# NSE2020_1.net
KiCad netlist of a schematic drawn in EAGLE
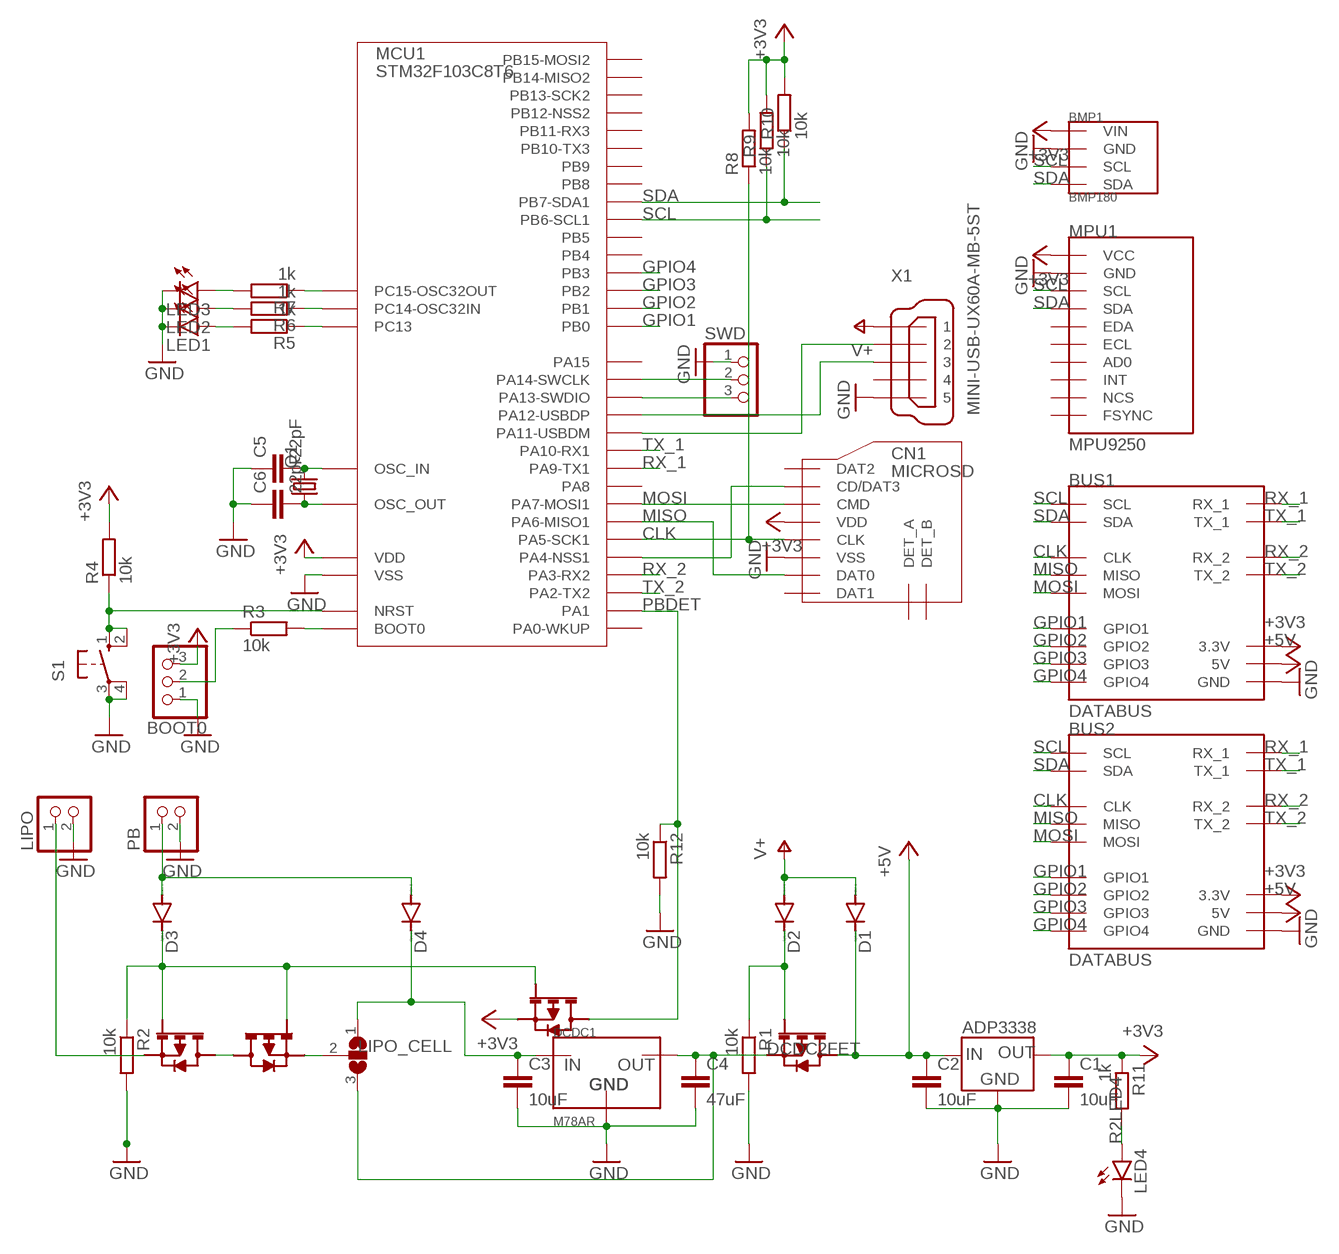
[diagram p0: schematic, sheet 1]

(export (version "E")
  (design (tool "Eeschema 10.0.6"))
  (components
    (comp (ref "BMP1")
      (value "BMP180")
      (footprint "eagle-import:GY-68")
      (libsource (lib "eagle-import") (part "BMP180"))
    )
    (comp (ref "BOOT0")
      (value "PINHD-1X3")
      (footprint "eagle-import:1X03")
      (libsource (lib "eagle-import") (part "PINHD-1X3"))
    )
    (comp (ref "BUS1")
      (value "DATABUS")
      (footprint "eagle-import:8X2")
      (libsource (lib "eagle-import") (part "DATABUS"))
    )
    (comp (ref "BUS2")
      (value "DATABUS")
      (footprint "eagle-import:8X2")
      (libsource (lib "eagle-import") (part "DATABUS"))
    )
    (comp (ref "C1")
      (value "10uF")
      (footprint "eagle-import:C2012")
      (libsource (lib "eagle-import") (part "C-EUC2012"))
    )
    (comp (ref "C2")
      (value "10uF")
      (footprint "eagle-import:C2012")
      (libsource (lib "eagle-import") (part "C-EUC2012"))
    )
    (comp (ref "C3")
      (value "10uF")
      (footprint "eagle-import:C2012")
      (libsource (lib "eagle-import") (part "C-EUC2012"))
    )
    (comp (ref "C4")
      (value "47uF")
      (footprint "eagle-import:C2012")
      (libsource (lib "eagle-import") (part "C-EUC2012"))
    )
    (comp (ref "C5")
      (value "22pF")
      (footprint "eagle-import:C2012")
      (libsource (lib "eagle-import") (part "C-EUC2012"))
    )
    (comp (ref "C6")
      (value "22pF")
      (footprint "eagle-import:C2012")
      (libsource (lib "eagle-import") (part "C-EUC2012"))
    )
    (comp (ref "CN1")
      (value "MICROSD")
      (footprint "eagle-import:DM3AT")
      (libsource (lib "eagle-import") (part "MICROSD"))
    )
    (comp (ref "D1")
      (value "DIODE-SOD123")
      (footprint "eagle-import:SOD123")
      (libsource (lib "eagle-import") (part "DIODE-SOD123"))
    )
    (comp (ref "D2")
      (value "DIODE-SOD123")
      (footprint "eagle-import:SOD123")
      (libsource (lib "eagle-import") (part "DIODE-SOD123"))
    )
    (comp (ref "D3")
      (value "DIODE-SOD123")
      (footprint "eagle-import:SOD123")
      (libsource (lib "eagle-import") (part "DIODE-SOD123"))
    )
    (comp (ref "D4")
      (value "DIODE-SOD123")
      (footprint "eagle-import:SOD123")
      (libsource (lib "eagle-import") (part "DIODE-SOD123"))
    )
    (comp (ref "DCDC1")
      (value "M78AR")
      (footprint "eagle-import:M78AR")
      (libsource (lib "eagle-import") (part "M78AR"))
    )
    (comp (ref "IC1")
      (value "ADP3338-3.3")
      (footprint "eagle-import:SOT-223")
      (libsource (lib "eagle-import") (part "ADP3338-3.3"))
    )
    (comp (ref "LED1")
      (value "LEDSMT1206")
      (footprint "eagle-import:1206")
      (libsource (lib "eagle-import") (part "LEDSMT1206"))
    )
    (comp (ref "LED2")
      (value "LEDSMT1206")
      (footprint "eagle-import:1206")
      (libsource (lib "eagle-import") (part "LEDSMT1206"))
    )
    (comp (ref "LED3")
      (value "LEDSMT1206")
      (footprint "eagle-import:1206")
      (libsource (lib "eagle-import") (part "LEDSMT1206"))
    )
    (comp (ref "LED4")
      (value "LEDSMT1206")
      (footprint "eagle-import:1206")
      (libsource (lib "eagle-import") (part "LEDSMT1206"))
    )
    (comp (ref "LIPO")
      (value "PINHD-1X2")
      (footprint "eagle-import:1X02")
      (libsource (lib "eagle-import") (part "PINHD-1X2"))
    )
    (comp (ref "LIPO_CELL")
      (value "SJ2W")
      (footprint "eagle-import:SJ_2")
      (libsource (lib "eagle-import") (part "SJ2W"))
    )
    (comp (ref "MCU1")
      (value "STM32F103C8T6")
      (footprint "eagle-import:LQFP48")
      (libsource (lib "eagle-import") (part "STM32F103C8T6"))
    )
    (comp (ref "MPU1")
      (value "MPU9250")
      (footprint "eagle-import:GY-9250")
      (libsource (lib "eagle-import") (part "MPU9250"))
    )
    (comp (ref "PB")
      (value "PINHD-1X2")
      (footprint "eagle-import:1X02")
      (libsource (lib "eagle-import") (part "PINHD-1X2"))
    )
    (comp (ref "Q1")
      (value "CRYSTALHC49S")
      (footprint "eagle-import:HC49_S")
      (libsource (lib "eagle-import") (part "CRYSTALHC49S"))
    )
    (comp (ref "R1")
      (value "10k")
      (footprint "eagle-import:M2012")
      (libsource (lib "eagle-import") (part "R-EU_M2012"))
    )
    (comp (ref "R2")
      (value "10k")
      (footprint "eagle-import:M2012")
      (libsource (lib "eagle-import") (part "R-EU_M2012"))
    )
    (comp (ref "R3")
      (value "10k")
      (footprint "eagle-import:M2012")
      (libsource (lib "eagle-import") (part "R-EU_M2012"))
    )
    (comp (ref "R4")
      (value "10k")
      (footprint "eagle-import:M2012")
      (libsource (lib "eagle-import") (part "R-EU_M2012"))
    )
    (comp (ref "R5")
      (value "1k")
      (footprint "eagle-import:M2012")
      (libsource (lib "eagle-import") (part "R-EU_M2012"))
    )
    (comp (ref "R6")
      (value "1k")
      (footprint "eagle-import:M2012")
      (libsource (lib "eagle-import") (part "R-EU_M2012"))
    )
    (comp (ref "R7")
      (value "1k")
      (footprint "eagle-import:M2012")
      (libsource (lib "eagle-import") (part "R-EU_M2012"))
    )
    (comp (ref "R8")
      (value "10k")
      (footprint "eagle-import:M2012")
      (libsource (lib "eagle-import") (part "R-EU_M2012"))
    )
    (comp (ref "R9")
      (value "10k")
      (footprint "eagle-import:M2012")
      (libsource (lib "eagle-import") (part "R-EU_M2012"))
    )
    (comp (ref "R10")
      (value "10k")
      (footprint "eagle-import:M2012")
      (libsource (lib "eagle-import") (part "R-EU_M2012"))
    )
    (comp (ref "R11")
      (value "1k")
      (footprint "eagle-import:M2012")
      (libsource (lib "eagle-import") (part "R-EU_M2012"))
    )
    (comp (ref "R12")
      (value "10k")
      (footprint "eagle-import:M2012")
      (libsource (lib "eagle-import") (part "R-EU_M2012"))
    )
    (comp (ref "S1")
      (value "10-XX")
      (footprint "eagle-import:B3F-10XX")
      (fields (field (name "MPN") "B3F-1000"))
      (libsource (lib "eagle-import") (part "10-XX"))
    )
    (comp (ref "SWD")
      (value "PINHD-1X3")
      (footprint "eagle-import:1X03")
      (libsource (lib "eagle-import") (part "PINHD-1X3"))
    )
    (comp (ref "U$1")
      (value "2SJ681")
      (footprint "eagle-import:2SJ681")
      (libsource (lib "eagle-import") (part "2SJ681"))
    )
    (comp (ref "U$2")
      (value "2SJ681")
      (footprint "eagle-import:2SJ681")
      (libsource (lib "eagle-import") (part "2SJ681"))
    )
    (comp (ref "U$3")
      (value "2SJ681")
      (footprint "eagle-import:2SJ681")
      (libsource (lib "eagle-import") (part "2SJ681"))
    )
    (comp (ref "U$4")
      (value "2SJ681")
      (footprint "eagle-import:2SJ681")
      (libsource (lib "eagle-import") (part "2SJ681"))
    )
    (comp (ref "X1")
      (value "MINI-USB-UX60A-MB-5ST")
      (footprint "eagle-import:UX60A-MB-5ST")
      (libsource (lib "eagle-import") (part "MINI-USB-UX60A-MB-5ST"))
    )
  )
  (nets
    (net (code "1") (name "+3V3") (class "Default")
      (node (ref "BMP1") (pin "P1") (pinfunction "VIN_P1") (pintype "bidirectional"))
      (node (ref "BOOT0") (pin "3") (pinfunction "3_3") (pintype "passive"))
      (node (ref "BUS1") (pin "P6") (pinfunction "3.3V_P6") (pintype "bidirectional"))
      (node (ref "BUS2") (pin "P6") (pinfunction "3.3V_P6") (pintype "bidirectional"))
      (node (ref "C1") (pin "1") (pinfunction "1_1") (pintype "passive"))
      (node (ref "CN1") (pin "VDD") (pinfunction "VDD_VDD") (pintype "bidirectional"))
      (node (ref "IC1") (pin "1") (pinfunction "OUT_1") (pintype "output"))
      (node (ref "IC1") (pin "2") (pinfunction "OUT_2") (pintype "output"))
      (node (ref "MCU1") (pin "1") (pinfunction "VDD_1") (pintype "bidirectional"))
      (node (ref "MCU1") (pin "24") (pinfunction "VDD_24") (pintype "bidirectional"))
      (node (ref "MCU1") (pin "36") (pinfunction "VDD_36") (pintype "bidirectional"))
      (node (ref "MCU1") (pin "48") (pinfunction "VDD_48") (pintype "bidirectional"))
      (node (ref "MCU1") (pin "9") (pinfunction "VDD_9") (pintype "bidirectional"))
      (node (ref "MPU1") (pin "P1") (pinfunction "VCC_P1") (pintype "bidirectional"))
      (node (ref "R10") (pin "2") (pinfunction "2_2") (pintype "passive"))
      (node (ref "R11") (pin "1") (pinfunction "1_1") (pintype "passive"))
      (node (ref "R4") (pin "2") (pinfunction "2_2") (pintype "passive"))
      (node (ref "R8") (pin "2") (pinfunction "2_2") (pintype "passive"))
      (node (ref "R9") (pin "2") (pinfunction "2_2") (pintype "passive"))
      (node (ref "U$4") (pin "P$3") (pinfunction "P$3_P$3") (pintype "bidirectional"))
    )
    (net (code "2") (name "+5V") (class "Default")
      (node (ref "BUS1") (pin "P7") (pinfunction "5V_P7") (pintype "bidirectional"))
      (node (ref "BUS2") (pin "P7") (pinfunction "5V_P7") (pintype "bidirectional"))
      (node (ref "C2") (pin "1") (pinfunction "1_1") (pintype "passive"))
      (node (ref "D1") (pin "C") (pinfunction "C_C") (pintype "passive"))
      (node (ref "IC1") (pin "3") (pinfunction "IN_3") (pintype "input"))
      (node (ref "U$1") (pin "P$2") (pinfunction "P$1_P$2") (pintype "bidirectional"))
      (node (ref "U$1") (pin "P$4") (pinfunction "P$1_P$4") (pintype "bidirectional"))
    )
    (net (code "3") (name "/CLK") (class "Default")
      (node (ref "BUS1") (pin "P1") (pinfunction "CLK_P1") (pintype "bidirectional"))
      (node (ref "BUS2") (pin "P1") (pinfunction "CLK_P1") (pintype "bidirectional"))
      (node (ref "CN1") (pin "CLK") (pinfunction "CLK_CLK") (pintype "bidirectional"))
      (node (ref "MCU1") (pin "15") (pinfunction "PA5-SCK1_15") (pintype "bidirectional"))
      (node (ref "R8") (pin "1") (pinfunction "1_1") (pintype "passive"))
    )
    (net (code "4") (name "/DCDC2FET") (class "Default")
      (node (ref "C4") (pin "1") (pinfunction "1_1") (pintype "passive"))
      (node (ref "DCDC1") (pin "P3") (pinfunction "OUT_P3") (pintype "bidirectional"))
      (node (ref "LIPO_CELL") (pin "3") (pinfunction "3_3") (pintype "passive"))
      (node (ref "U$1") (pin "P$3") (pinfunction "P$3_P$3") (pintype "bidirectional"))
    )
    (net (code "5") (name "/GPIO1") (class "Default")
      (node (ref "BUS1") (pin "P3") (pinfunction "GPIO1_P3") (pintype "bidirectional"))
      (node (ref "BUS2") (pin "P3") (pinfunction "GPIO1_P3") (pintype "bidirectional"))
      (node (ref "MCU1") (pin "18") (pinfunction "PB0_18") (pintype "bidirectional"))
    )
    (net (code "6") (name "/GPIO2") (class "Default")
      (node (ref "BUS1") (pin "P10") (pinfunction "GPIO2_P10") (pintype "bidirectional"))
      (node (ref "BUS2") (pin "P10") (pinfunction "GPIO2_P10") (pintype "bidirectional"))
      (node (ref "MCU1") (pin "19") (pinfunction "PB1_19") (pintype "bidirectional"))
    )
    (net (code "7") (name "/GPIO3") (class "Default")
      (node (ref "BUS1") (pin "P14") (pinfunction "GPIO3_P14") (pintype "bidirectional"))
      (node (ref "BUS2") (pin "P14") (pinfunction "GPIO3_P14") (pintype "bidirectional"))
      (node (ref "MCU1") (pin "20") (pinfunction "PB2_20") (pintype "bidirectional"))
    )
    (net (code "8") (name "/GPIO4") (class "Default")
      (node (ref "BUS1") (pin "P15") (pinfunction "GPIO4_P15") (pintype "bidirectional"))
      (node (ref "BUS2") (pin "P15") (pinfunction "GPIO4_P15") (pintype "bidirectional"))
      (node (ref "MCU1") (pin "39") (pinfunction "PB3_39") (pintype "bidirectional"))
    )
    (net (code "9") (name "/MISO") (class "Default")
      (node (ref "BUS1") (pin "P12") (pinfunction "MISO_P12") (pintype "bidirectional"))
      (node (ref "BUS2") (pin "P12") (pinfunction "MISO_P12") (pintype "bidirectional"))
      (node (ref "CN1") (pin "DAT0") (pinfunction "DAT0_DAT0") (pintype "bidirectional"))
      (node (ref "MCU1") (pin "16") (pinfunction "PA6-MISO1_16") (pintype "bidirectional"))
    )
    (net (code "10") (name "/MOSI") (class "Default")
      (node (ref "BUS1") (pin "P2") (pinfunction "MOSI_P2") (pintype "bidirectional"))
      (node (ref "BUS2") (pin "P2") (pinfunction "MOSI_P2") (pintype "bidirectional"))
      (node (ref "CN1") (pin "CMD") (pinfunction "CMD_CMD") (pintype "bidirectional"))
      (node (ref "MCU1") (pin "17") (pinfunction "PA7-MOSI1_17") (pintype "bidirectional"))
    )
    (net (code "11") (name "/PBDET") (class "Default")
      (node (ref "MCU1") (pin "11") (pinfunction "PA1_11") (pintype "bidirectional"))
      (node (ref "R12") (pin "1") (pinfunction "1_1") (pintype "passive"))
      (node (ref "U$4") (pin "P$2") (pinfunction "P$1_P$2") (pintype "bidirectional"))
      (node (ref "U$4") (pin "P$4") (pinfunction "P$1_P$4") (pintype "bidirectional"))
    )
    (net (code "12") (name "/R2LED4") (class "Default")
      (node (ref "LED4") (pin "A") (pinfunction "A_A") (pintype "passive"))
      (node (ref "R11") (pin "2") (pinfunction "2_2") (pintype "passive"))
    )
    (net (code "13") (name "/RX_1") (class "Default")
      (node (ref "BUS1") (pin "P4") (pinfunction "RX_1_P4") (pintype "bidirectional"))
      (node (ref "BUS2") (pin "P4") (pinfunction "RX_1_P4") (pintype "bidirectional"))
      (node (ref "MCU1") (pin "30") (pinfunction "PA9-TX1_30") (pintype "bidirectional"))
    )
    (net (code "14") (name "/RX_2") (class "Default")
      (node (ref "BUS1") (pin "P9") (pinfunction "RX_2_P9") (pintype "bidirectional"))
      (node (ref "BUS2") (pin "P9") (pinfunction "RX_2_P9") (pintype "bidirectional"))
      (node (ref "MCU1") (pin "13") (pinfunction "PA3-RX2_13") (pintype "bidirectional"))
    )
    (net (code "15") (name "/SCL") (class "Default")
      (node (ref "BMP1") (pin "P3") (pinfunction "SCL_P3") (pintype "bidirectional"))
      (node (ref "BUS1") (pin "P0") (pinfunction "SCL_P0") (pintype "bidirectional"))
      (node (ref "BUS2") (pin "P0") (pinfunction "SCL_P0") (pintype "bidirectional"))
      (node (ref "MCU1") (pin "42") (pinfunction "PB6-SCL1_42") (pintype "bidirectional"))
      (node (ref "MPU1") (pin "P3") (pinfunction "SCL_P3") (pintype "bidirectional"))
      (node (ref "R9") (pin "1") (pinfunction "1_1") (pintype "passive"))
    )
    (net (code "16") (name "/SDA") (class "Default")
      (node (ref "BMP1") (pin "P4") (pinfunction "SDA_P4") (pintype "bidirectional"))
      (node (ref "BUS1") (pin "P13") (pinfunction "SDA_P13") (pintype "bidirectional"))
      (node (ref "BUS2") (pin "P13") (pinfunction "SDA_P13") (pintype "bidirectional"))
      (node (ref "MCU1") (pin "43") (pinfunction "PB7-SDA1_43") (pintype "bidirectional"))
      (node (ref "MPU1") (pin "P4") (pinfunction "SDA_P4") (pintype "bidirectional"))
      (node (ref "R10") (pin "1") (pinfunction "1_1") (pintype "passive"))
    )
    (net (code "17") (name "/TX_1") (class "Default")
      (node (ref "BUS1") (pin "P5") (pinfunction "TX_1_P5") (pintype "bidirectional"))
      (node (ref "BUS2") (pin "P5") (pinfunction "TX_1_P5") (pintype "bidirectional"))
      (node (ref "MCU1") (pin "31") (pinfunction "PA10-RX1_31") (pintype "bidirectional"))
    )
    (net (code "18") (name "/TX_2") (class "Default")
      (node (ref "BUS1") (pin "P8") (pinfunction "TX_2_P8") (pintype "bidirectional"))
      (node (ref "BUS2") (pin "P8") (pinfunction "TX_2_P8") (pintype "bidirectional"))
      (node (ref "MCU1") (pin "12") (pinfunction "PA2-TX2_12") (pintype "bidirectional"))
    )
    (net (code "19") (name "GND") (class "Default")
      (node (ref "BMP1") (pin "P2") (pinfunction "GND_P2") (pintype "bidirectional"))
      (node (ref "BOOT0") (pin "1") (pinfunction "1_1") (pintype "passive"))
      (node (ref "BUS1") (pin "P11") (pinfunction "GND_P11") (pintype "bidirectional"))
      (node (ref "BUS2") (pin "P11") (pinfunction "GND_P11") (pintype "bidirectional"))
      (node (ref "C1") (pin "2") (pinfunction "2_2") (pintype "passive"))
      (node (ref "C2") (pin "2") (pinfunction "2_2") (pintype "passive"))
      (node (ref "C3") (pin "2") (pinfunction "2_2") (pintype "passive"))
      (node (ref "C4") (pin "2") (pinfunction "2_2") (pintype "passive"))
      (node (ref "C5") (pin "1") (pinfunction "1_1") (pintype "passive"))
      (node (ref "C6") (pin "1") (pinfunction "1_1") (pintype "passive"))
      (node (ref "CN1") (pin "VSS") (pinfunction "VSS_VSS") (pintype "bidirectional"))
      (node (ref "DCDC1") (pin "P2") (pinfunction "GND_P2") (pintype "bidirectional"))
      (node (ref "IC1") (pin "4") (pinfunction "GND_4") (pintype "bidirectional"))
      (node (ref "LED1") (pin "C") (pinfunction "C_C") (pintype "passive"))
      (node (ref "LED2") (pin "C") (pinfunction "C_C") (pintype "passive"))
      (node (ref "LED3") (pin "C") (pinfunction "C_C") (pintype "passive"))
      (node (ref "LED4") (pin "C") (pinfunction "C_C") (pintype "passive"))
      (node (ref "LIPO") (pin "2") (pinfunction "2_2") (pintype "passive"))
      (node (ref "MCU1") (pin "23") (pinfunction "VSS_23") (pintype "bidirectional"))
      (node (ref "MCU1") (pin "35") (pinfunction "VSS_35") (pintype "bidirectional"))
      (node (ref "MCU1") (pin "47") (pinfunction "VSS_47") (pintype "bidirectional"))
      (node (ref "MCU1") (pin "8") (pinfunction "VSS_8") (pintype "bidirectional"))
      (node (ref "MPU1") (pin "P10") (pinfunction "GND_P10") (pintype "bidirectional"))
      (node (ref "PB") (pin "2") (pinfunction "2_2") (pintype "passive"))
      (node (ref "R1") (pin "2") (pinfunction "2_2") (pintype "passive"))
      (node (ref "R12") (pin "2") (pinfunction "2_2") (pintype "passive"))
      (node (ref "R2") (pin "2") (pinfunction "2_2") (pintype "passive"))
      (node (ref "S1") (pin "3") (pinfunction "P_3") (pintype "passive"))
      (node (ref "S1") (pin "4") (pinfunction "P1_4") (pintype "passive"))
      (node (ref "SWD") (pin "1") (pinfunction "1_1") (pintype "passive"))
      (node (ref "X1") (pin "5") (pinfunction "5_5") (pintype "input"))
    )
    (net (code "20") (name "Net-(BOOT0-Pad2)") (class "Default")
      (node (ref "BOOT0") (pin "2") (pinfunction "2_2") (pintype "passive"))
      (node (ref "R3") (pin "1") (pinfunction "1_1") (pintype "passive"))
    )
    (net (code "21") (name "Net-(D3-PadA)") (class "Default")
      (node (ref "D3") (pin "A") (pinfunction "A_A") (pintype "passive"))
      (node (ref "D4") (pin "A") (pinfunction "A_A") (pintype "passive"))
      (node (ref "PB") (pin "1") (pinfunction "1_1") (pintype "passive"))
    )
    (net (code "22") (name "Net-(DCDC1-IN)") (class "Default")
      (node (ref "C3") (pin "1") (pinfunction "1_1") (pintype "passive"))
      (node (ref "D4") (pin "C") (pinfunction "C_C") (pintype "passive"))
      (node (ref "DCDC1") (pin "P1") (pinfunction "IN_P1") (pintype "bidirectional"))
      (node (ref "LIPO_CELL") (pin "1") (pinfunction "1_1") (pintype "passive"))
    )
    (net (code "23") (name "Net-(LED1-PadA)") (class "Default")
      (node (ref "LED1") (pin "A") (pinfunction "A_A") (pintype "passive"))
      (node (ref "R5") (pin "2") (pinfunction "2_2") (pintype "passive"))
    )
    (net (code "24") (name "Net-(LED2-PadA)") (class "Default")
      (node (ref "LED2") (pin "A") (pinfunction "A_A") (pintype "passive"))
      (node (ref "R6") (pin "2") (pinfunction "2_2") (pintype "passive"))
    )
    (net (code "25") (name "Net-(LED3-PadA)") (class "Default")
      (node (ref "LED3") (pin "A") (pinfunction "A_A") (pintype "passive"))
      (node (ref "R7") (pin "2") (pinfunction "2_2") (pintype "passive"))
    )
    (net (code "26") (name "Net-(LIPO-Pad1)") (class "Default")
      (node (ref "LIPO") (pin "1") (pinfunction "1_1") (pintype "passive"))
      (node (ref "U$3") (pin "P$3") (pinfunction "P$3_P$3") (pintype "bidirectional"))
    )
    (net (code "27") (name "Net-(LIPO_CELL-Pad2)") (class "Default")
      (node (ref "LIPO_CELL") (pin "2") (pinfunction "2_2") (pintype "passive"))
      (node (ref "U$2") (pin "P$3") (pinfunction "P$3_P$3") (pintype "bidirectional"))
    )
    (net (code "28") (name "Net-(MCU1-BOOT0)") (class "Default")
      (node (ref "MCU1") (pin "44") (pinfunction "BOOT0_44") (pintype "bidirectional"))
      (node (ref "R3") (pin "2") (pinfunction "2_2") (pintype "passive"))
    )
    (net (code "29") (name "Net-(MCU1-NRST)") (class "Default")
      (node (ref "MCU1") (pin "7") (pinfunction "NRST_7") (pintype "bidirectional"))
      (node (ref "R4") (pin "1") (pinfunction "1_1") (pintype "passive"))
      (node (ref "S1") (pin "1") (pinfunction "S_1") (pintype "passive"))
      (node (ref "S1") (pin "2") (pinfunction "S1_2") (pintype "passive"))
    )
    (net (code "30") (name "Net-(MCU1-OSC_IN)") (class "Default")
      (node (ref "C5") (pin "2") (pinfunction "2_2") (pintype "passive"))
      (node (ref "MCU1") (pin "5") (pinfunction "OSC_IN_5") (pintype "bidirectional"))
      (node (ref "Q1") (pin "2") (pinfunction "2_2") (pintype "passive"))
    )
    (net (code "31") (name "Net-(MCU1-OSC_OUT)") (class "Default")
      (node (ref "C6") (pin "2") (pinfunction "2_2") (pintype "passive"))
      (node (ref "MCU1") (pin "6") (pinfunction "OSC_OUT_6") (pintype "bidirectional"))
      (node (ref "Q1") (pin "1") (pinfunction "1_1") (pintype "passive"))
    )
    (net (code "32") (name "Net-(MCU1-PA4-NSS1)") (class "Default")
      (node (ref "CN1") (pin "CD/DAT3") (pinfunction "CD/DAT3_CD/DAT3") (pintype "bidirectional"))
      (node (ref "MCU1") (pin "14") (pinfunction "PA4-NSS1_14") (pintype "bidirectional"))
    )
    (net (code "33") (name "Net-(MCU1-PA11-USBDM)") (class "Default")
      (node (ref "MCU1") (pin "32") (pinfunction "PA11-USBDM_32") (pintype "bidirectional"))
      (node (ref "X1") (pin "2") (pinfunction "2_2") (pintype "input"))
    )
    (net (code "34") (name "Net-(MCU1-PA12-USBDP)") (class "Default")
      (node (ref "MCU1") (pin "33") (pinfunction "PA12-USBDP_33") (pintype "bidirectional"))
      (node (ref "X1") (pin "3") (pinfunction "3_3") (pintype "input"))
    )
    (net (code "35") (name "Net-(MCU1-PA13-SWDIO)") (class "Default")
      (node (ref "MCU1") (pin "34") (pinfunction "PA13-SWDIO_34") (pintype "bidirectional"))
      (node (ref "SWD") (pin "3") (pinfunction "3_3") (pintype "passive"))
    )
    (net (code "36") (name "Net-(MCU1-PA14-SWCLK)") (class "Default")
      (node (ref "MCU1") (pin "37") (pinfunction "PA14-SWCLK_37") (pintype "bidirectional"))
      (node (ref "SWD") (pin "2") (pinfunction "2_2") (pintype "passive"))
    )
    (net (code "37") (name "Net-(MCU1-PC13)") (class "Default")
      (node (ref "MCU1") (pin "2") (pinfunction "PC13_2") (pintype "bidirectional"))
      (node (ref "R5") (pin "1") (pinfunction "1_1") (pintype "passive"))
    )
    (net (code "38") (name "Net-(MCU1-PC14-OSC32IN)") (class "Default")
      (node (ref "MCU1") (pin "3") (pinfunction "PC14-OSC32IN_3") (pintype "bidirectional"))
      (node (ref "R6") (pin "1") (pinfunction "1_1") (pintype "passive"))
    )
    (net (code "39") (name "Net-(MCU1-PC15-OSC32OUT)") (class "Default")
      (node (ref "MCU1") (pin "4") (pinfunction "PC15-OSC32OUT_4") (pintype "bidirectional"))
      (node (ref "R7") (pin "1") (pinfunction "1_1") (pintype "passive"))
    )
    (net (code "40") (name "Net-(U$1-P$2)") (class "Default")
      (node (ref "D2") (pin "C") (pinfunction "C_C") (pintype "passive"))
      (node (ref "R1") (pin "1") (pinfunction "1_1") (pintype "passive"))
      (node (ref "U$1") (pin "P$1") (pinfunction "P$2_P$1") (pintype "bidirectional"))
    )
    (net (code "41") (name "Net-(U$2-P$1-PadP$2)") (class "Default")
      (node (ref "U$2") (pin "P$2") (pinfunction "P$1_P$2") (pintype "bidirectional"))
      (node (ref "U$2") (pin "P$4") (pinfunction "P$1_P$4") (pintype "bidirectional"))
      (node (ref "U$3") (pin "P$2") (pinfunction "P$1_P$2") (pintype "bidirectional"))
      (node (ref "U$3") (pin "P$4") (pinfunction "P$1_P$4") (pintype "bidirectional"))
    )
    (net (code "42") (name "Net-(U$2-P$2)") (class "Default")
      (node (ref "D3") (pin "C") (pinfunction "C_C") (pintype "passive"))
      (node (ref "R2") (pin "1") (pinfunction "1_1") (pintype "passive"))
      (node (ref "U$2") (pin "P$1") (pinfunction "P$2_P$1") (pintype "bidirectional"))
      (node (ref "U$3") (pin "P$1") (pinfunction "P$2_P$1") (pintype "bidirectional"))
      (node (ref "U$4") (pin "P$1") (pinfunction "P$2_P$1") (pintype "bidirectional"))
    )
    (net (code "43") (name "V+") (class "Default")
      (node (ref "D1") (pin "A") (pinfunction "A_A") (pintype "passive"))
      (node (ref "D2") (pin "A") (pinfunction "A_A") (pintype "passive"))
      (node (ref "X1") (pin "1") (pinfunction "1_1") (pintype "input"))
    )
    (net (code "44") (name "unconnected-(CN1-PadDAT1)") (class "Default")
      (node (ref "CN1") (pin "DAT1") (pinfunction "DAT1_DAT1") (pintype "bidirectional"))
    )
    (net (code "45") (name "unconnected-(CN1-PadDAT2)") (class "Default")
      (node (ref "CN1") (pin "DAT2") (pinfunction "DAT2_DAT2") (pintype "bidirectional"))
    )
    (net (code "46") (name "unconnected-(CN1-PadDET_A)") (class "Default")
      (node (ref "CN1") (pin "DET_A") (pinfunction "DET_A_DET_A") (pintype "bidirectional"))
    )
    (net (code "47") (name "unconnected-(CN1-PadDET_B)") (class "Default")
      (node (ref "CN1") (pin "DET_B") (pinfunction "DET_B_DET_B") (pintype "bidirectional"))
    )
    (net (code "48") (name "unconnected-(MCU1-PA0-WKUP-Pad10)") (class "Default")
      (node (ref "MCU1") (pin "10") (pinfunction "PA0-WKUP_10") (pintype "bidirectional"))
    )
    (net (code "49") (name "unconnected-(MCU1-PA8-Pad29)") (class "Default")
      (node (ref "MCU1") (pin "29") (pinfunction "PA8_29") (pintype "bidirectional"))
    )
    (net (code "50") (name "unconnected-(MCU1-PA15-Pad38)") (class "Default")
      (node (ref "MCU1") (pin "38") (pinfunction "PA15_38") (pintype "bidirectional"))
    )
    (net (code "51") (name "unconnected-(MCU1-PB4-Pad40)") (class "Default")
      (node (ref "MCU1") (pin "40") (pinfunction "PB4_40") (pintype "bidirectional"))
    )
    (net (code "52") (name "unconnected-(MCU1-PB5-Pad41)") (class "Default")
      (node (ref "MCU1") (pin "41") (pinfunction "PB5_41") (pintype "bidirectional"))
    )
    (net (code "53") (name "unconnected-(MCU1-PB8-Pad45)") (class "Default")
      (node (ref "MCU1") (pin "45") (pinfunction "PB8_45") (pintype "bidirectional"))
    )
    (net (code "54") (name "unconnected-(MCU1-PB9-Pad46)") (class "Default")
      (node (ref "MCU1") (pin "46") (pinfunction "PB9_46") (pintype "bidirectional"))
    )
    (net (code "55") (name "unconnected-(MCU1-PB10-TX3-Pad21)") (class "Default")
      (node (ref "MCU1") (pin "21") (pinfunction "PB10-TX3_21") (pintype "bidirectional"))
    )
    (net (code "56") (name "unconnected-(MCU1-PB11-RX3-Pad22)") (class "Default")
      (node (ref "MCU1") (pin "22") (pinfunction "PB11-RX3_22") (pintype "bidirectional"))
    )
    (net (code "57") (name "unconnected-(MCU1-PB12-NSS2-Pad25)") (class "Default")
      (node (ref "MCU1") (pin "25") (pinfunction "PB12-NSS2_25") (pintype "bidirectional"))
    )
    (net (code "58") (name "unconnected-(MCU1-PB13-SCK2-Pad26)") (class "Default")
      (node (ref "MCU1") (pin "26") (pinfunction "PB13-SCK2_26") (pintype "bidirectional"))
    )
    (net (code "59") (name "unconnected-(MCU1-PB14-MISO2-Pad27)") (class "Default")
      (node (ref "MCU1") (pin "27") (pinfunction "PB14-MISO2_27") (pintype "bidirectional"))
    )
    (net (code "60") (name "unconnected-(MCU1-PB15-MOSI2-Pad28)") (class "Default")
      (node (ref "MCU1") (pin "28") (pinfunction "PB15-MOSI2_28") (pintype "bidirectional"))
    )
    (net (code "61") (name "unconnected-(MPU1-AD0-PadP2)") (class "Default")
      (node (ref "MPU1") (pin "P2") (pinfunction "AD0_P2") (pintype "bidirectional"))
    )
    (net (code "62") (name "unconnected-(MPU1-ECL-PadP5)") (class "Default")
      (node (ref "MPU1") (pin "P5") (pinfunction "ECL_P5") (pintype "bidirectional"))
    )
    (net (code "63") (name "unconnected-(MPU1-EDA-PadP6)") (class "Default")
      (node (ref "MPU1") (pin "P6") (pinfunction "EDA_P6") (pintype "bidirectional"))
    )
    (net (code "64") (name "unconnected-(MPU1-FSYNC-PadP7)") (class "Default")
      (node (ref "MPU1") (pin "P7") (pinfunction "FSYNC_P7") (pintype "bidirectional"))
    )
    (net (code "65") (name "unconnected-(MPU1-INT-PadP8)") (class "Default")
      (node (ref "MPU1") (pin "P8") (pinfunction "INT_P8") (pintype "bidirectional"))
    )
    (net (code "66") (name "unconnected-(MPU1-NCS-PadP9)") (class "Default")
      (node (ref "MPU1") (pin "P9") (pinfunction "NCS_P9") (pintype "bidirectional"))
    )
    (net (code "67") (name "unconnected-(X1-Pad4)") (class "Default")
      (node (ref "X1") (pin "4") (pinfunction "4_4") (pintype "input"))
    )
  )
)
